# 24.net
KiCad netlist of a schematic drawn in Altium Designer
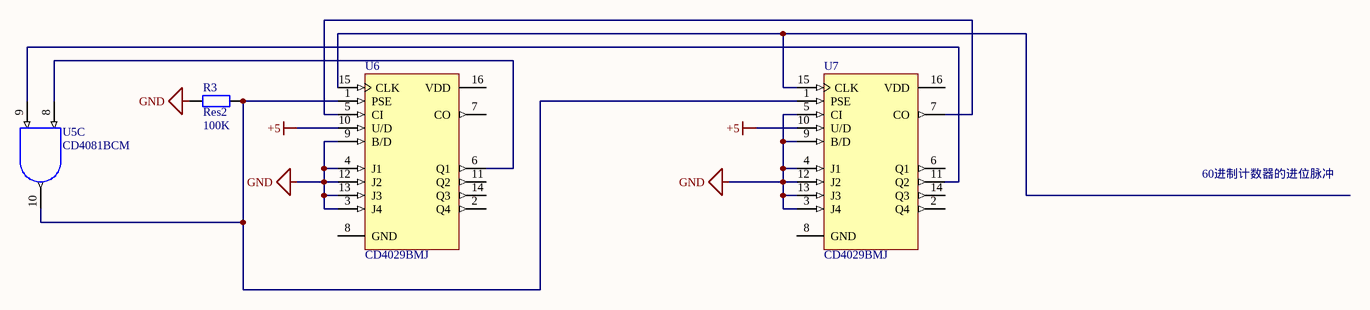
[diagram p0: 24进制计数器.SchDoc]

(export (version "E")
  (design (tool "Eeschema 10.0.6"))
  (components
    (comp (ref "R3")
      (value "Res2")
      (footprint "AXIAL-0.4")
      (description "Resistor")
      (fields (field (name "ALTIUM_VALUE") "100K") (field (name "PUBLISHER") "Altium Limited"))
      (libsource (lib "Miscellaneous Devices") (part "Res2"))
    )
    (comp (ref "U5")
      (value "CD4081BCM")
      (footprint "M14A_N")
      (description "Quad 2-Input AND Buffered B series Gate, 14-Pin SOIC")
      (fields (field (name "PUBLISHER") "Altium Limited"))
      (libsource (lib "FSC Logic Gate") (part "CD4081BCM"))
    )
    (comp (ref "U6")
      (value "CD4029BMJ")
      (footprint "J16A")
      (description "Binary/Decade Up/Down Counter")
      (fields (field (name "PUBLISHER") "Altium Limited"))
      (libsource (lib "NSC Logic Counter") (part "CD4029BMJ"))
    )
    (comp (ref "U7")
      (value "CD4029BMJ")
      (footprint "J16A")
      (description "Binary/Decade Up/Down Counter")
      (fields (field (name "PUBLISHER") "Altium Limited"))
      (libsource (lib "NSC Logic Counter") (part "CD4029BMJ"))
    )
  )
  (nets
    (net (code "1") (name "+5") (class "Default")
      (node (ref "U6") (pin "10") (pinfunction "U/D_10") (pintype "input"))
      (node (ref "U7") (pin "10") (pinfunction "U/D_10") (pintype "input"))
    )
    (net (code "2") (name "GND") (class "Default")
      (node (ref "R3") (pin "1") (pinfunction "1_1") (pintype "passive"))
      (node (ref "U5") (pin "7") (pinfunction "GND_7") (pintype "power_in"))
      (node (ref "U6") (pin "12") (pinfunction "J2_12") (pintype "input"))
      (node (ref "U6") (pin "13") (pinfunction "J3_13") (pintype "input"))
      (node (ref "U6") (pin "3") (pinfunction "J4_3") (pintype "input"))
      (node (ref "U6") (pin "4") (pinfunction "J1_4") (pintype "input"))
      (node (ref "U6") (pin "9") (pinfunction "B/D_9") (pintype "input"))
      (node (ref "U7") (pin "12") (pinfunction "J2_12") (pintype "input"))
      (node (ref "U7") (pin "13") (pinfunction "J3_13") (pintype "input"))
      (node (ref "U7") (pin "3") (pinfunction "J4_3") (pintype "input"))
      (node (ref "U7") (pin "4") (pinfunction "J1_4") (pintype "input"))
      (node (ref "U7") (pin "5") (pinfunction "CI_5") (pintype "input"))
      (node (ref "U7") (pin "9") (pinfunction "B/D_9") (pintype "input"))
    )
    (net (code "3") (name "Net-(U5C-A)") (class "Default")
      (node (ref "U5") (pin "8") (pinfunction "A_8") (pintype "input"))
      (node (ref "U6") (pin "6") (pinfunction "Q1_6") (pintype "output"))
    )
    (net (code "4") (name "Net-(U5C-B)") (class "Default")
      (node (ref "U5") (pin "9") (pinfunction "B_9") (pintype "input"))
      (node (ref "U7") (pin "11") (pinfunction "Q2_11") (pintype "output"))
    )
    (net (code "5") (name "Net-(U5C-J)") (class "Default")
      (node (ref "R3") (pin "2") (pinfunction "2_2") (pintype "passive"))
      (node (ref "U5") (pin "10") (pinfunction "J_10") (pintype "output"))
      (node (ref "U6") (pin "1") (pinfunction "PSE_1") (pintype "input"))
      (node (ref "U7") (pin "1") (pinfunction "PSE_1") (pintype "input"))
    )
    (net (code "6") (name "Net-(U6-CI)") (class "Default")
      (node (ref "U6") (pin "5") (pinfunction "CI_5") (pintype "input"))
      (node (ref "U7") (pin "7") (pinfunction "CO_7") (pintype "output"))
    )
    (net (code "7") (name "Net-(U6-CLK)") (class "Default")
      (node (ref "U6") (pin "15") (pinfunction "CLK_15") (pintype "input"))
      (node (ref "U7") (pin "15") (pinfunction "CLK_15") (pintype "input"))
    )
    (net (code "8") (name "VDD") (class "Default")
      (node (ref "U5") (pin "14") (pinfunction "VDD_14") (pintype "power_in"))
    )
    (net (code "9") (name "unconnected-(U6-CO-Pad7)") (class "Default")
      (node (ref "U6") (pin "7") (pinfunction "CO_7") (pintype "output"))
    )
    (net (code "10") (name "unconnected-(U6-GND-Pad8)") (class "Default")
      (node (ref "U6") (pin "8") (pinfunction "GND_8") (pintype "power_in"))
    )
    (net (code "11") (name "unconnected-(U6-Q2-Pad11)") (class "Default")
      (node (ref "U6") (pin "11") (pinfunction "Q2_11") (pintype "output"))
    )
    (net (code "12") (name "unconnected-(U6-Q3-Pad14)") (class "Default")
      (node (ref "U6") (pin "14") (pinfunction "Q3_14") (pintype "output"))
    )
    (net (code "13") (name "unconnected-(U6-Q4-Pad2)") (class "Default")
      (node (ref "U6") (pin "2") (pinfunction "Q4_2") (pintype "output"))
    )
    (net (code "14") (name "unconnected-(U6-VDD-Pad16)") (class "Default")
      (node (ref "U6") (pin "16") (pinfunction "VDD_16") (pintype "power_in"))
    )
    (net (code "15") (name "unconnected-(U7-GND-Pad8)") (class "Default")
      (node (ref "U7") (pin "8") (pinfunction "GND_8") (pintype "power_in"))
    )
    (net (code "16") (name "unconnected-(U7-Q1-Pad6)") (class "Default")
      (node (ref "U7") (pin "6") (pinfunction "Q1_6") (pintype "output"))
    )
    (net (code "17") (name "unconnected-(U7-Q3-Pad14)") (class "Default")
      (node (ref "U7") (pin "14") (pinfunction "Q3_14") (pintype "output"))
    )
    (net (code "18") (name "unconnected-(U7-Q4-Pad2)") (class "Default")
      (node (ref "U7") (pin "2") (pinfunction "Q4_2") (pintype "output"))
    )
    (net (code "19") (name "unconnected-(U7-VDD-Pad16)") (class "Default")
      (node (ref "U7") (pin "16") (pinfunction "VDD_16") (pintype "power_in"))
    )
  )
)
